# RSP_antithept.net
KiCad netlist of a schematic drawn in EAGLE
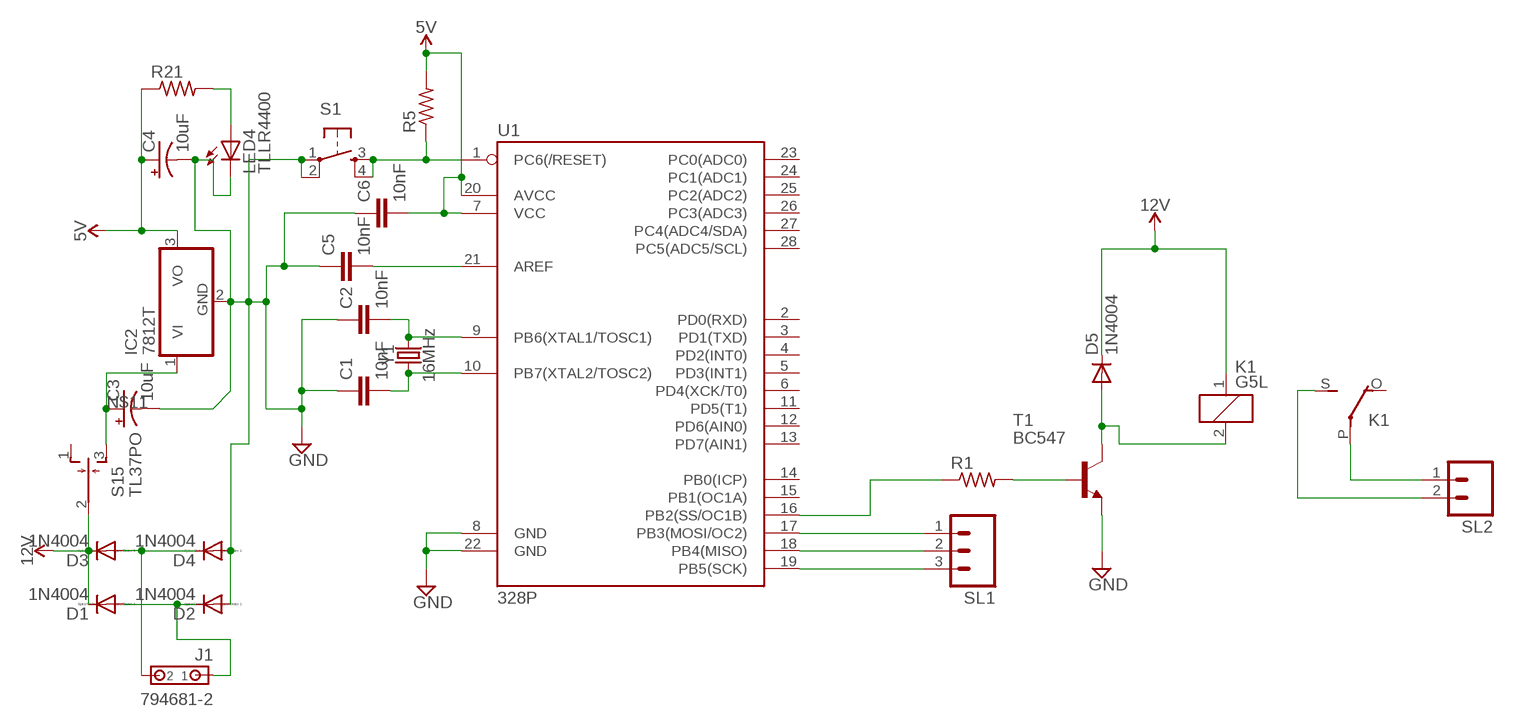
[diagram p0: schematic, sheet 1]

(export (version "E")
  (design (tool "Eeschema 10.0.6"))
  (components
    (comp (ref "C1")
      (value "10nF")
      (footprint "eagle-import:CAP-PTH-10MM")
      (libsource (lib "eagle-import") (part "10NF-PTH-10MM-10000V-1-%"))
    )
    (comp (ref "C2")
      (value "10nF")
      (footprint "eagle-import:CAP-PTH-10MM")
      (libsource (lib "eagle-import") (part "10NF-PTH-10MM-10000V-1-%"))
    )
    (comp (ref "C3")
      (value "10uF")
      (footprint "eagle-import:CPOL-RADIAL-2.5MM-5MM-KIT")
      (libsource (lib "eagle-import") (part "10UF-POLAR-RADIAL-2.5MM-KIT-25V-20%"))
    )
    (comp (ref "C4")
      (value "10uF")
      (footprint "eagle-import:CPOL-RADIAL-2.5MM-5MM-KIT")
      (libsource (lib "eagle-import") (part "10UF-POLAR-RADIAL-2.5MM-KIT-25V-20%"))
    )
    (comp (ref "C5")
      (value "10nF")
      (footprint "eagle-import:CAP-PTH-10MM")
      (libsource (lib "eagle-import") (part "10NF-PTH-10MM-10000V-1-%"))
    )
    (comp (ref "C6")
      (value "10nF")
      (footprint "eagle-import:CAP-PTH-10MM")
      (libsource (lib "eagle-import") (part "10NF-PTH-10MM-10000V-1-%"))
    )
    (comp (ref "D1")
      (value "1N4004")
      (footprint "eagle-import:DO41-10")
      (libsource (lib "eagle-import") (part "1N4004"))
    )
    (comp (ref "D2")
      (value "1N4004")
      (footprint "eagle-import:DO41-10")
      (libsource (lib "eagle-import") (part "1N4004"))
    )
    (comp (ref "D3")
      (value "1N4004")
      (footprint "eagle-import:DO41-10")
      (libsource (lib "eagle-import") (part "1N4004"))
    )
    (comp (ref "D4")
      (value "1N4004")
      (footprint "eagle-import:DO41-10")
      (libsource (lib "eagle-import") (part "1N4004"))
    )
    (comp (ref "D5")
      (value "1N4004")
      (footprint "eagle-import:DO41-10")
      (libsource (lib "eagle-import") (part "diode-1_1N4004"))
    )
    (comp (ref "IC2")
      (value "7812T")
      (footprint "eagle-import:TO220H")
      (libsource (lib "eagle-import") (part "78T12"))
    )
    (comp (ref "J1")
      (value "794681-2")
      (footprint "eagle-import:794681-2")
      (libsource (lib "eagle-import") (part "794681-2"))
    )
    (comp (ref "K1")
      (value "G5L")
      (footprint "eagle-import:G5LE")
      (libsource (lib "eagle-import") (part "G5L"))
    )
    (comp (ref "LED4")
      (value "TLLR4400")
      (footprint "eagle-import:LED3MM")
      (fields (field (name "MF") "VISHAY SEMICONDUCTOR"))
      (libsource (lib "eagle-import") (part "TLLR4400"))
    )
    (comp (ref "R1")
      (value "R-US_0207/9")
      (footprint "eagle-import:0207_9")
      (libsource (lib "eagle-import") (part "R-US_0207/9"))
    )
    (comp (ref "R5")
      (value "R-US_0207/12")
      (footprint "eagle-import:0207_12")
      (libsource (lib "eagle-import") (part "rcl_R-US_0207/12"))
    )
    (comp (ref "R21")
      (value "R-US_0207/12")
      (footprint "eagle-import:0207_12")
      (libsource (lib "eagle-import") (part "rcl_R-US_0207/12"))
    )
    (comp (ref "S1")
      (value "TAC_SWITCHPTH")
      (footprint "eagle-import:TACTILE-PTH")
      (libsource (lib "eagle-import") (part "TAC_SWITCHPTH"))
    )
    (comp (ref "S15")
      (value "TL37PO")
      (footprint "eagle-import:TL3XPO")
      (libsource (lib "eagle-import") (part "TL37PO"))
    )
    (comp (ref "SL1")
      (value "MA03")
      (footprint "eagle-import:03P")
      (libsource (lib "eagle-import") (part "MA03"))
    )
    (comp (ref "SL2")
      (value "MA02")
      (footprint "eagle-import:02PA")
      (libsource (lib "eagle-import") (part "MA02"))
    )
    (comp (ref "T1")
      (value "BC547")
      (footprint "eagle-import:TO92")
      (libsource (lib "eagle-import") (part "BC547"))
    )
    (comp (ref "U1")
      (value "328P")
      (footprint "eagle-import:DIP28")
      (libsource (lib "eagle-import") (part "ATMEGA328P_PDIP"))
    )
    (comp (ref "Y1")
      (value "16MHz")
      (footprint "eagle-import:HC49US")
      (libsource (lib "eagle-import") (part "CRYSTAL-16MHZPTH-HC49US"))
    )
  )
  (nets
    (net (code "1") (name "/N$11") (class "Default")
      (node (ref "C3") (pin "1") (pinfunction "+_1") (pintype "passive"))
      (node (ref "IC2") (pin "1") (pinfunction "VI_1") (pintype "input"))
      (node (ref "S15") (pin "3") (pinfunction "S_3") (pintype "passive"))
    )
    (net (code "2") (name "5V") (class "Default")
      (node (ref "C4") (pin "1") (pinfunction "+_1") (pintype "passive"))
      (node (ref "C6") (pin "2") (pinfunction "2_2") (pintype "passive"))
      (node (ref "IC2") (pin "3") (pinfunction "VO_3") (pintype "passive"))
      (node (ref "R21") (pin "1") (pinfunction "1_1") (pintype "passive"))
      (node (ref "R5") (pin "2") (pinfunction "2_2") (pintype "passive"))
      (node (ref "U1") (pin "20") (pinfunction "AVCC_20") (pintype "bidirectional"))
      (node (ref "U1") (pin "7") (pinfunction "VCC_7") (pintype "bidirectional"))
    )
    (net (code "3") (name "12V") (class "Default")
      (node (ref "D1") (pin "C") (pinfunction "C_C") (pintype "passive"))
      (node (ref "D3") (pin "C") (pinfunction "C_C") (pintype "passive"))
      (node (ref "D5") (pin "C") (pinfunction "C_C") (pintype "passive"))
      (node (ref "K1") (pin "1") (pinfunction "1_1") (pintype "passive"))
      (node (ref "S15") (pin "2") (pinfunction "P_2") (pintype "passive"))
    )
    (net (code "4") (name "GND") (class "Default")
      (node (ref "C1") (pin "1") (pinfunction "1_1") (pintype "passive"))
      (node (ref "C2") (pin "1") (pinfunction "1_1") (pintype "passive"))
      (node (ref "C3") (pin "2") (pinfunction "-_2") (pintype "passive"))
      (node (ref "C4") (pin "2") (pinfunction "-_2") (pintype "passive"))
      (node (ref "C5") (pin "1") (pinfunction "1_1") (pintype "passive"))
      (node (ref "C6") (pin "1") (pinfunction "1_1") (pintype "passive"))
      (node (ref "D2") (pin "A") (pinfunction "A_A") (pintype "passive"))
      (node (ref "D4") (pin "A") (pinfunction "A_A") (pintype "passive"))
      (node (ref "IC2") (pin "2") (pinfunction "GND_2") (pintype "passive"))
      (node (ref "LED4") (pin "K") (pinfunction "C_K") (pintype "passive"))
      (node (ref "S1") (pin "1") (pinfunction "1_1") (pintype "passive"))
      (node (ref "S1") (pin "2") (pinfunction "2_2") (pintype "passive"))
      (node (ref "T1") (pin "1") (pinfunction "E_1") (pintype "passive"))
      (node (ref "U1") (pin "22") (pinfunction "GND_22") (pintype "bidirectional"))
      (node (ref "U1") (pin "8") (pinfunction "GND_8") (pintype "bidirectional"))
    )
    (net (code "5") (name "Net-(D1-PadA)") (class "Default")
      (node (ref "D1") (pin "A") (pinfunction "A_A") (pintype "passive"))
      (node (ref "D2") (pin "C") (pinfunction "C_C") (pintype "passive"))
      (node (ref "J1") (pin "1") (pinfunction "1_1") (pintype "passive"))
    )
    (net (code "6") (name "Net-(D3-PadA)") (class "Default")
      (node (ref "D3") (pin "A") (pinfunction "A_A") (pintype "passive"))
      (node (ref "D4") (pin "C") (pinfunction "C_C") (pintype "passive"))
      (node (ref "J1") (pin "2") (pinfunction "2_2") (pintype "passive"))
    )
    (net (code "7") (name "Net-(K1-PadP)") (class "Default")
      (node (ref "K1") (pin "P") (pinfunction "P_P") (pintype "passive"))
      (node (ref "SL2") (pin "1") (pinfunction "1_1") (pintype "passive"))
    )
    (net (code "8") (name "Net-(K1-PadS)") (class "Default")
      (node (ref "K1") (pin "S") (pinfunction "S_S") (pintype "passive"))
      (node (ref "SL2") (pin "2") (pinfunction "2_2") (pintype "passive"))
    )
    (net (code "9") (name "Net-(LED4-PadA)") (class "Default")
      (node (ref "LED4") (pin "A") (pinfunction "A_A") (pintype "passive"))
      (node (ref "R21") (pin "2") (pinfunction "2_2") (pintype "passive"))
    )
    (net (code "10") (name "Net-(T1-B)") (class "Default")
      (node (ref "R1") (pin "2") (pinfunction "2_2") (pintype "passive"))
      (node (ref "T1") (pin "2") (pinfunction "B_2") (pintype "passive"))
    )
    (net (code "11") (name "Net-(T1-C)") (class "Default")
      (node (ref "D5") (pin "A") (pinfunction "A_A") (pintype "passive"))
      (node (ref "K1") (pin "2") (pinfunction "2_2") (pintype "passive"))
      (node (ref "T1") (pin "3") (pinfunction "C_3") (pintype "passive"))
    )
    (net (code "12") (name "Net-(U1-AREF)") (class "Default")
      (node (ref "C5") (pin "2") (pinfunction "2_2") (pintype "passive"))
      (node (ref "U1") (pin "21") (pinfunction "AREF_21") (pintype "bidirectional"))
    )
    (net (code "13") (name "Net-(U1-PB2(SS{slash}OC1B))") (class "Default")
      (node (ref "R1") (pin "1") (pinfunction "1_1") (pintype "passive"))
      (node (ref "U1") (pin "16") (pinfunction "PB2(SS/OC1B)_16") (pintype "bidirectional"))
    )
    (net (code "14") (name "Net-(U1-PB3(MOSI{slash}OC2))") (class "Default")
      (node (ref "SL1") (pin "1") (pinfunction "1_1") (pintype "passive"))
      (node (ref "U1") (pin "17") (pinfunction "PB3(MOSI/OC2)_17") (pintype "bidirectional"))
    )
    (net (code "15") (name "Net-(U1-PB4(MISO))") (class "Default")
      (node (ref "SL1") (pin "2") (pinfunction "2_2") (pintype "passive"))
      (node (ref "U1") (pin "18") (pinfunction "PB4(MISO)_18") (pintype "bidirectional"))
    )
    (net (code "16") (name "Net-(U1-PB5(SCK))") (class "Default")
      (node (ref "SL1") (pin "3") (pinfunction "3_3") (pintype "passive"))
      (node (ref "U1") (pin "19") (pinfunction "PB5(SCK)_19") (pintype "bidirectional"))
    )
    (net (code "17") (name "Net-(U1-PB6(XTAL1{slash}TOSC1))") (class "Default")
      (node (ref "C2") (pin "2") (pinfunction "2_2") (pintype "passive"))
      (node (ref "U1") (pin "9") (pinfunction "PB6(XTAL1/TOSC1)_9") (pintype "bidirectional"))
      (node (ref "Y1") (pin "2") (pinfunction "2_2") (pintype "passive"))
    )
    (net (code "18") (name "Net-(U1-PB7(XTAL2{slash}TOSC2))") (class "Default")
      (node (ref "C1") (pin "2") (pinfunction "2_2") (pintype "passive"))
      (node (ref "U1") (pin "10") (pinfunction "PB7(XTAL2/TOSC2)_10") (pintype "bidirectional"))
      (node (ref "Y1") (pin "1") (pinfunction "1_1") (pintype "passive"))
    )
    (net (code "19") (name "Net-(U1-PC6({slash}RESET))") (class "Default")
      (node (ref "R5") (pin "1") (pinfunction "1_1") (pintype "passive"))
      (node (ref "S1") (pin "3") (pinfunction "3_3") (pintype "passive"))
      (node (ref "S1") (pin "4") (pinfunction "4_4") (pintype "passive"))
      (node (ref "U1") (pin "1") (pinfunction "PC6(/RESET)_1") (pintype "bidirectional"))
    )
    (net (code "20") (name "unconnected-(K1-PadO)") (class "Default")
      (node (ref "K1") (pin "O") (pinfunction "O_O") (pintype "passive"))
    )
    (net (code "21") (name "unconnected-(S15-O-Pad1)") (class "Default")
      (node (ref "S15") (pin "1") (pinfunction "O_1") (pintype "passive"))
    )
    (net (code "22") (name "unconnected-(U1-PB0(ICP)-Pad14)") (class "Default")
      (node (ref "U1") (pin "14") (pinfunction "PB0(ICP)_14") (pintype "bidirectional"))
    )
    (net (code "23") (name "unconnected-(U1-PB1(OC1A)-Pad15)") (class "Default")
      (node (ref "U1") (pin "15") (pinfunction "PB1(OC1A)_15") (pintype "bidirectional"))
    )
    (net (code "24") (name "unconnected-(U1-PC0(ADC0)-Pad23)") (class "Default")
      (node (ref "U1") (pin "23") (pinfunction "PC0(ADC0)_23") (pintype "bidirectional"))
    )
    (net (code "25") (name "unconnected-(U1-PC1(ADC1)-Pad24)") (class "Default")
      (node (ref "U1") (pin "24") (pinfunction "PC1(ADC1)_24") (pintype "bidirectional"))
    )
    (net (code "26") (name "unconnected-(U1-PC2(ADC2)-Pad25)") (class "Default")
      (node (ref "U1") (pin "25") (pinfunction "PC2(ADC2)_25") (pintype "bidirectional"))
    )
    (net (code "27") (name "unconnected-(U1-PC3(ADC3)-Pad26)") (class "Default")
      (node (ref "U1") (pin "26") (pinfunction "PC3(ADC3)_26") (pintype "bidirectional"))
    )
    (net (code "28") (name "unconnected-(U1-PC4(ADC4{slash}SDA)-Pad27)") (class "Default")
      (node (ref "U1") (pin "27") (pinfunction "PC4(ADC4/SDA)_27") (pintype "bidirectional"))
    )
    (net (code "29") (name "unconnected-(U1-PC5(ADC5{slash}SCL)-Pad28)") (class "Default")
      (node (ref "U1") (pin "28") (pinfunction "PC5(ADC5/SCL)_28") (pintype "bidirectional"))
    )
    (net (code "30") (name "unconnected-(U1-PD0(RXD)-Pad2)") (class "Default")
      (node (ref "U1") (pin "2") (pinfunction "PD0(RXD)_2") (pintype "bidirectional"))
    )
    (net (code "31") (name "unconnected-(U1-PD1(TXD)-Pad3)") (class "Default")
      (node (ref "U1") (pin "3") (pinfunction "PD1(TXD)_3") (pintype "bidirectional"))
    )
    (net (code "32") (name "unconnected-(U1-PD2(INT0)-Pad4)") (class "Default")
      (node (ref "U1") (pin "4") (pinfunction "PD2(INT0)_4") (pintype "bidirectional"))
    )
    (net (code "33") (name "unconnected-(U1-PD3(INT1)-Pad5)") (class "Default")
      (node (ref "U1") (pin "5") (pinfunction "PD3(INT1)_5") (pintype "bidirectional"))
    )
    (net (code "34") (name "unconnected-(U1-PD4(XCK{slash}T0)-Pad6)") (class "Default")
      (node (ref "U1") (pin "6") (pinfunction "PD4(XCK/T0)_6") (pintype "bidirectional"))
    )
    (net (code "35") (name "unconnected-(U1-PD5(T1)-Pad11)") (class "Default")
      (node (ref "U1") (pin "11") (pinfunction "PD5(T1)_11") (pintype "bidirectional"))
    )
    (net (code "36") (name "unconnected-(U1-PD6(AIN0)-Pad12)") (class "Default")
      (node (ref "U1") (pin "12") (pinfunction "PD6(AIN0)_12") (pintype "bidirectional"))
    )
    (net (code "37") (name "unconnected-(U1-PD7(AIN1)-Pad13)") (class "Default")
      (node (ref "U1") (pin "13") (pinfunction "PD7(AIN1)_13") (pintype "bidirectional"))
    )
  )
)
